# utilidong-ftdi-uart-lipo-charger-mk-1_0.net
KiCad netlist of a schematic drawn in EAGLE
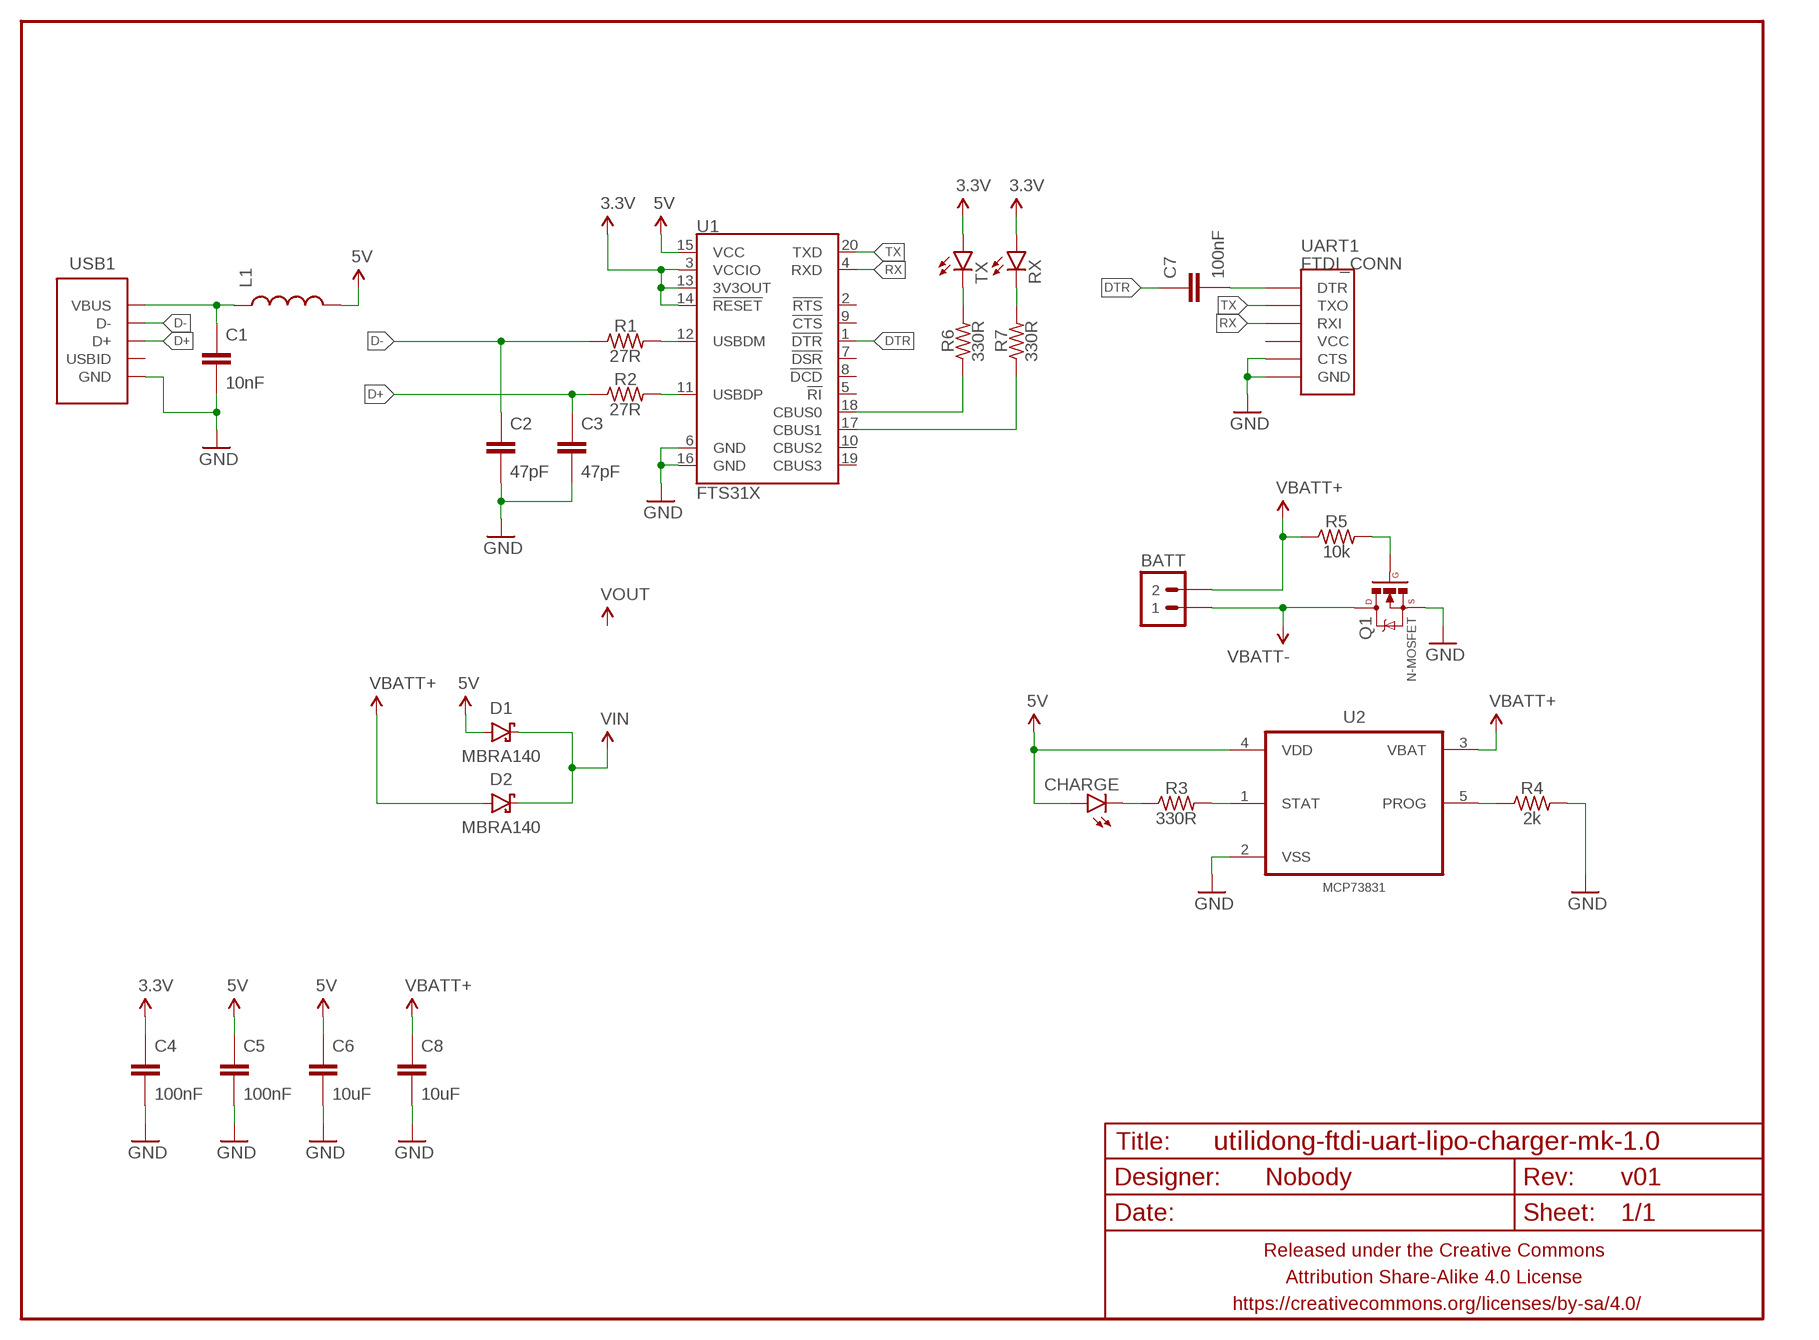
[diagram p0: schematic, sheet 1]

(export (version "E")
  (design (tool "Eeschema 10.0.6"))
  (components
    (comp (ref "BATT")
      (value "M02PTH-CENTERED-R+")
      (footprint "eagle-import:1X02-CENTER-R+")
      (libsource (lib "eagle-import") (part "M02PTH-CENTERED-R+"))
    )
    (comp (ref "C1")
      (value "10nF")
      (footprint "eagle-import:C0805")
      (libsource (lib "eagle-import") (part "CAPACITOR-CERAMICC0805"))
    )
    (comp (ref "C2")
      (value "47pF")
      (footprint "eagle-import:C0805")
      (libsource (lib "eagle-import") (part "CAPACITOR-CERAMICC0805"))
    )
    (comp (ref "C3")
      (value "47pF")
      (footprint "eagle-import:C0805")
      (libsource (lib "eagle-import") (part "CAPACITOR-CERAMICC0805"))
    )
    (comp (ref "C4")
      (value "100nF")
      (footprint "eagle-import:C0805")
      (libsource (lib "eagle-import") (part "CAPACITOR-CERAMICC0805"))
    )
    (comp (ref "C5")
      (value "100nF")
      (footprint "eagle-import:C0805")
      (libsource (lib "eagle-import") (part "CAPACITOR-CERAMICC0805"))
    )
    (comp (ref "C6")
      (value "10uF")
      (footprint "eagle-import:C0805")
      (libsource (lib "eagle-import") (part "CAPACITOR-CERAMICC0805"))
    )
    (comp (ref "C7")
      (value "100nF")
      (footprint "eagle-import:C0805")
      (libsource (lib "eagle-import") (part "CAPACITOR-CERAMICC0805"))
    )
    (comp (ref "C8")
      (value "10uF")
      (footprint "eagle-import:C0805")
      (libsource (lib "eagle-import") (part "CAPACITOR-CERAMICC0805"))
    )
    (comp (ref "CHARGE")
      (value "LED1206")
      (footprint "eagle-import:LED-1206")
      (libsource (lib "eagle-import") (part "LED1206"))
    )
    (comp (ref "D1")
      (value "MBRA140")
      (footprint "eagle-import:SMA-DIODE")
      (libsource (lib "eagle-import") (part "DIODE-SCHOTTKYMBRA140"))
    )
    (comp (ref "D2")
      (value "MBRA140")
      (footprint "eagle-import:SMA-DIODE")
      (libsource (lib "eagle-import") (part "DIODE-SCHOTTKYMBRA140"))
    )
    (comp (ref "FRAME1")
      (value "FRAME-LETTERNO_PACKAGE")
      (footprint "eagle-import:DUMMY")
      (fields (field (name "DESIGNER") "Nobody"))
      (libsource (lib "eagle-import") (part "FRAME-LETTERNO_PACKAGE"))
    )
    (comp (ref "L1")
      (value "INDUCTORL0805")
      (footprint "eagle-import:L0805")
      (libsource (lib "eagle-import") (part "INDUCTORL0805"))
    )
    (comp (ref "Q1")
      (value "N-MOSFET")
      (footprint "eagle-import:SOT23")
      (libsource (lib "eagle-import") (part "MOSFET-NCHANNELBSS138"))
    )
    (comp (ref "R1")
      (value "27R")
      (footprint "eagle-import:R0805")
      (libsource (lib "eagle-import") (part "RESISTORR0805"))
    )
    (comp (ref "R2")
      (value "27R")
      (footprint "eagle-import:R0805")
      (libsource (lib "eagle-import") (part "RESISTORR0805"))
    )
    (comp (ref "R3")
      (value "330R")
      (footprint "eagle-import:R0805")
      (libsource (lib "eagle-import") (part "RESISTORR0805"))
    )
    (comp (ref "R4")
      (value "2k")
      (footprint "eagle-import:R0805")
      (libsource (lib "eagle-import") (part "RESISTORR0805"))
    )
    (comp (ref "R5")
      (value "10k")
      (footprint "eagle-import:R0805")
      (libsource (lib "eagle-import") (part "RESISTORR0805"))
    )
    (comp (ref "R6")
      (value "330R")
      (footprint "eagle-import:R0805")
      (libsource (lib "eagle-import") (part "RESISTORR0805"))
    )
    (comp (ref "R7")
      (value "330R")
      (footprint "eagle-import:R0805")
      (libsource (lib "eagle-import") (part "RESISTORR0805"))
    )
    (comp (ref "RX")
      (value "LED1206")
      (footprint "eagle-import:LED-1206")
      (libsource (lib "eagle-import") (part "LED1206"))
    )
    (comp (ref "TX")
      (value "LED1206")
      (footprint "eagle-import:LED-1206")
      (libsource (lib "eagle-import") (part "LED1206"))
    )
    (comp (ref "U1")
      (value "FTS31X")
      (footprint "eagle-import:SSOP20_L")
      (libsource (lib "eagle-import") (part "FT231XS"))
    )
    (comp (ref "U2")
      (value "MCP73831")
      (footprint "eagle-import:SOT95P280X145-5N")
      (fields (field (name "MPN") "MCP73831T-2ACI/OT"))
      (libsource (lib "eagle-import") (part "MCP73831T-2ACI/OT"))
    )
    (comp (ref "UART1")
      (value "FTDI_CONN")
      (footprint "eagle-import:FTDI_CONN")
      (libsource (lib "eagle-import") (part "FTDI_CONN"))
    )
    (comp (ref "USB1")
      (value "USB-ABCOMBO")
      (footprint "eagle-import:USB-MICRO-B-FCI-CUTOUT")
      (libsource (lib "eagle-import") (part "USB-ABCOMBO"))
    )
  )
  (nets
    (net (code "1") (name "3.3V") (class "Default")
      (node (ref "C4") (pin "1") (pinfunction "1_1") (pintype "passive"))
      (node (ref "RX") (pin "A") (pinfunction "A_A") (pintype "passive"))
      (node (ref "TX") (pin "A") (pinfunction "A_A") (pintype "passive"))
      (node (ref "U1") (pin "13") (pinfunction "3V3OUT_13") (pintype "bidirectional"))
      (node (ref "U1") (pin "14") (pinfunction "~{RESET}_14") (pintype "bidirectional"))
      (node (ref "U1") (pin "3") (pinfunction "VCCIO_3") (pintype "bidirectional"))
    )
    (net (code "2") (name "5V") (class "Default")
      (node (ref "C5") (pin "1") (pinfunction "1_1") (pintype "passive"))
      (node (ref "C6") (pin "1") (pinfunction "1_1") (pintype "passive"))
      (node (ref "CHARGE") (pin "A") (pinfunction "A_A") (pintype "passive"))
      (node (ref "D1") (pin "A") (pinfunction "A_A") (pintype "passive"))
      (node (ref "L1") (pin "2") (pinfunction "2_2") (pintype "passive"))
      (node (ref "U1") (pin "15") (pinfunction "VCC_15") (pintype "bidirectional"))
      (node (ref "U2") (pin "4") (pinfunction "VDD_4") (pintype "power_in"))
    )
    (net (code "3") (name "D+") (class "Default")
      (node (ref "C3") (pin "1") (pinfunction "1_1") (pintype "passive"))
      (node (ref "R2") (pin "1") (pinfunction "1_1") (pintype "passive"))
      (node (ref "USB1") (pin "3") (pinfunction "D+_3") (pintype "bidirectional"))
    )
    (net (code "4") (name "D-") (class "Default")
      (node (ref "C2") (pin "1") (pinfunction "1_1") (pintype "passive"))
      (node (ref "R1") (pin "1") (pinfunction "1_1") (pintype "passive"))
      (node (ref "USB1") (pin "2") (pinfunction "D-_2") (pintype "bidirectional"))
    )
    (net (code "5") (name "DTR") (class "Default")
      (node (ref "C7") (pin "1") (pinfunction "1_1") (pintype "passive"))
      (node (ref "U1") (pin "1") (pinfunction "~{DTR}_1") (pintype "bidirectional"))
    )
    (net (code "6") (name "GND") (class "Default")
      (node (ref "C1") (pin "2") (pinfunction "2_2") (pintype "passive"))
      (node (ref "C2") (pin "2") (pinfunction "2_2") (pintype "passive"))
      (node (ref "C3") (pin "2") (pinfunction "2_2") (pintype "passive"))
      (node (ref "C4") (pin "2") (pinfunction "2_2") (pintype "passive"))
      (node (ref "C5") (pin "2") (pinfunction "2_2") (pintype "passive"))
      (node (ref "C6") (pin "2") (pinfunction "2_2") (pintype "passive"))
      (node (ref "C8") (pin "2") (pinfunction "2_2") (pintype "passive"))
      (node (ref "Q1") (pin "2") (pinfunction "S_2") (pintype "passive"))
      (node (ref "R4") (pin "2") (pinfunction "2_2") (pintype "passive"))
      (node (ref "U1") (pin "16") (pinfunction "GND_16") (pintype "bidirectional"))
      (node (ref "U1") (pin "6") (pinfunction "GND_6") (pintype "bidirectional"))
      (node (ref "U2") (pin "2") (pinfunction "VSS_2") (pintype "power_in"))
      (node (ref "UART1") (pin "CTS") (pinfunction "CTS_CTS") (pintype "bidirectional"))
      (node (ref "UART1") (pin "GND") (pinfunction "GND_GND") (pintype "bidirectional"))
      (node (ref "USB1") (pin "5") (pinfunction "GND_5") (pintype "bidirectional"))
      (node (ref "USB1") (pin "P$1") (pinfunction "GND_P$1") (pintype "bidirectional"))
      (node (ref "USB1") (pin "P$2") (pinfunction "GND_P$2") (pintype "bidirectional"))
    )
    (net (code "7") (name "Net-(C7-Pad2)") (class "Default")
      (node (ref "C7") (pin "2") (pinfunction "2_2") (pintype "passive"))
      (node (ref "UART1") (pin "DTR") (pinfunction "DTR_DTR") (pintype "bidirectional"))
    )
    (net (code "8") (name "Net-(CHARGE-PadC)") (class "Default")
      (node (ref "CHARGE") (pin "C") (pinfunction "C_C") (pintype "passive"))
      (node (ref "R3") (pin "1") (pinfunction "1_1") (pintype "passive"))
    )
    (net (code "9") (name "Net-(Q1-G)") (class "Default")
      (node (ref "Q1") (pin "1") (pinfunction "G_1") (pintype "passive"))
      (node (ref "R5") (pin "2") (pinfunction "2_2") (pintype "passive"))
    )
    (net (code "10") (name "Net-(R6-Pad2)") (class "Default")
      (node (ref "R6") (pin "2") (pinfunction "2_2") (pintype "passive"))
      (node (ref "TX") (pin "C") (pinfunction "C_C") (pintype "passive"))
    )
    (net (code "11") (name "Net-(R7-Pad2)") (class "Default")
      (node (ref "R7") (pin "2") (pinfunction "2_2") (pintype "passive"))
      (node (ref "RX") (pin "C") (pinfunction "C_C") (pintype "passive"))
    )
    (net (code "12") (name "Net-(U1-CBUS0)") (class "Default")
      (node (ref "R6") (pin "1") (pinfunction "1_1") (pintype "passive"))
      (node (ref "U1") (pin "18") (pinfunction "CBUS0_18") (pintype "bidirectional"))
    )
    (net (code "13") (name "Net-(U1-CBUS1)") (class "Default")
      (node (ref "R7") (pin "1") (pinfunction "1_1") (pintype "passive"))
      (node (ref "U1") (pin "17") (pinfunction "CBUS1_17") (pintype "bidirectional"))
    )
    (net (code "14") (name "Net-(U1-USBDM)") (class "Default")
      (node (ref "R1") (pin "2") (pinfunction "2_2") (pintype "passive"))
      (node (ref "U1") (pin "12") (pinfunction "USBDM_12") (pintype "bidirectional"))
    )
    (net (code "15") (name "Net-(U1-USBDP)") (class "Default")
      (node (ref "R2") (pin "2") (pinfunction "2_2") (pintype "passive"))
      (node (ref "U1") (pin "11") (pinfunction "USBDP_11") (pintype "bidirectional"))
    )
    (net (code "16") (name "Net-(U2-PROG)") (class "Default")
      (node (ref "R4") (pin "1") (pinfunction "1_1") (pintype "passive"))
      (node (ref "U2") (pin "5") (pinfunction "PROG_5") (pintype "input"))
    )
    (net (code "17") (name "Net-(U2-STAT)") (class "Default")
      (node (ref "R3") (pin "2") (pinfunction "2_2") (pintype "passive"))
      (node (ref "U2") (pin "1") (pinfunction "STAT_1") (pintype "output"))
    )
    (net (code "18") (name "Net-(USB1-VBUS)") (class "Default")
      (node (ref "C1") (pin "1") (pinfunction "1_1") (pintype "passive"))
      (node (ref "L1") (pin "1") (pinfunction "1_1") (pintype "passive"))
      (node (ref "USB1") (pin "1") (pinfunction "VBUS_1") (pintype "bidirectional"))
    )
    (net (code "19") (name "RX") (class "Default")
      (node (ref "U1") (pin "4") (pinfunction "RXD_4") (pintype "bidirectional"))
      (node (ref "UART1") (pin "RXI") (pinfunction "RXI_RXI") (pintype "bidirectional"))
    )
    (net (code "20") (name "TX") (class "Default")
      (node (ref "U1") (pin "20") (pinfunction "TXD_20") (pintype "bidirectional"))
      (node (ref "UART1") (pin "TXO") (pinfunction "TXO_TXO") (pintype "bidirectional"))
    )
    (net (code "21") (name "VBATT+") (class "Default")
      (node (ref "BATT") (pin "2") (pinfunction "2_2") (pintype "passive"))
      (node (ref "C8") (pin "1") (pinfunction "1_1") (pintype "passive"))
      (node (ref "D2") (pin "A") (pinfunction "A_A") (pintype "passive"))
      (node (ref "R5") (pin "1") (pinfunction "1_1") (pintype "passive"))
      (node (ref "U2") (pin "3") (pinfunction "VBAT_3") (pintype "output"))
    )
    (net (code "22") (name "VBATT-") (class "Default")
      (node (ref "BATT") (pin "1") (pinfunction "1_1") (pintype "passive"))
      (node (ref "Q1") (pin "3") (pinfunction "D_3") (pintype "passive"))
    )
    (net (code "23") (name "VIN") (class "Default")
      (node (ref "D1") (pin "C") (pinfunction "C_C") (pintype "passive"))
      (node (ref "D2") (pin "C") (pinfunction "C_C") (pintype "passive"))
    )
    (net (code "25") (name "unconnected-(U1-CBUS2-Pad10)") (class "Default")
      (node (ref "U1") (pin "10") (pinfunction "CBUS2_10") (pintype "bidirectional"))
    )
    (net (code "26") (name "unconnected-(U1-CBUS3-Pad19)") (class "Default")
      (node (ref "U1") (pin "19") (pinfunction "CBUS3_19") (pintype "bidirectional"))
    )
    (net (code "27") (name "unconnected-(U1-~{CTS}-Pad9)") (class "Default")
      (node (ref "U1") (pin "9") (pinfunction "~{CTS}_9") (pintype "bidirectional"))
    )
    (net (code "28") (name "unconnected-(U1-~{DCD}-Pad8)") (class "Default")
      (node (ref "U1") (pin "8") (pinfunction "~{DCD}_8") (pintype "bidirectional"))
    )
    (net (code "29") (name "unconnected-(U1-~{DSR}-Pad7)") (class "Default")
      (node (ref "U1") (pin "7") (pinfunction "~{DSR}_7") (pintype "bidirectional"))
    )
    (net (code "30") (name "unconnected-(U1-~{RI}-Pad5)") (class "Default")
      (node (ref "U1") (pin "5") (pinfunction "~{RI}_5") (pintype "bidirectional"))
    )
    (net (code "31") (name "unconnected-(U1-~{RTS}-Pad2)") (class "Default")
      (node (ref "U1") (pin "2") (pinfunction "~{RTS}_2") (pintype "bidirectional"))
    )
    (net (code "32") (name "unconnected-(UART1-PadVCC)") (class "Default")
      (node (ref "UART1") (pin "VCC") (pinfunction "VCC_VCC") (pintype "bidirectional"))
    )
    (net (code "33") (name "unconnected-(USB1-USBID-Pad4)") (class "Default")
      (node (ref "USB1") (pin "4") (pinfunction "USBID_4") (pintype "bidirectional"))
    )
  )
)
